# Pump_Control_Circuit.net
KiCad netlist of a schematic drawn in EAGLE
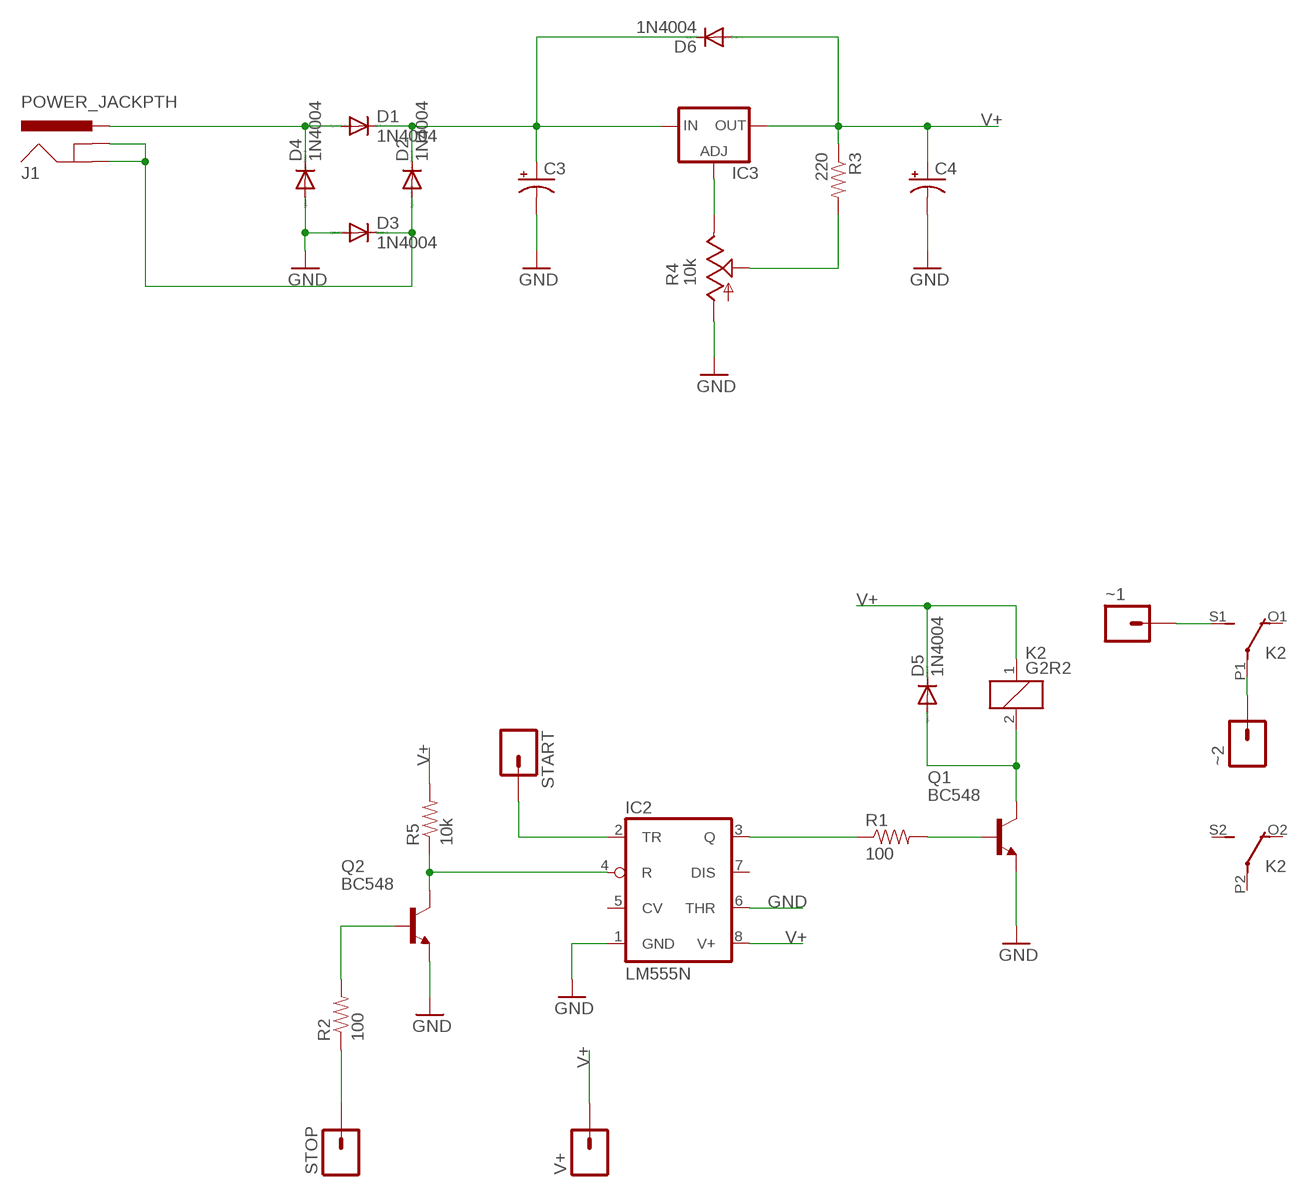
[diagram p0: schematic, sheet 1]

(export (version "E")
  (design (tool "Eeschema 10.0.6"))
  (components
    (comp (ref "C3")
      (value "CAP_POLPTH1")
      (footprint "eagle-import:CPOL-RADIAL-100UF-25V")
      (libsource (lib "eagle-import") (part "CAP_POLPTH1"))
    )
    (comp (ref "C4")
      (value "CAP_POLPTH4")
      (footprint "eagle-import:CPOL-RADIAL-1000UF-25V")
      (libsource (lib "eagle-import") (part "CAP_POLPTH4"))
    )
    (comp (ref "D1")
      (value "1N4004")
      (footprint "eagle-import:DO41-10")
      (libsource (lib "eagle-import") (part "1N4004"))
    )
    (comp (ref "D2")
      (value "1N4004")
      (footprint "eagle-import:DO41-10")
      (libsource (lib "eagle-import") (part "1N4004"))
    )
    (comp (ref "D3")
      (value "1N4004")
      (footprint "eagle-import:DO41-10")
      (libsource (lib "eagle-import") (part "1N4004"))
    )
    (comp (ref "D4")
      (value "1N4004")
      (footprint "eagle-import:DO41-10")
      (libsource (lib "eagle-import") (part "1N4004"))
    )
    (comp (ref "D5")
      (value "1N4004")
      (footprint "eagle-import:DO41-10")
      (libsource (lib "eagle-import") (part "1N4004"))
    )
    (comp (ref "D6")
      (value "1N4004")
      (footprint "eagle-import:DO41-10")
      (libsource (lib "eagle-import") (part "1N4004"))
    )
    (comp (ref "IC2")
      (value "LM555N")
      (footprint "eagle-import:DIL08")
      (libsource (lib "eagle-import") (part "555NLM"))
    )
    (comp (ref "IC3")
      (value "LM317TS")
      (footprint "eagle-import:317TS")
      (libsource (lib "eagle-import") (part "LM317TS"))
    )
    (comp (ref "J1")
      (value "POWER_JACKPTH")
      (footprint "eagle-import:POWER_JACK_PTH")
      (libsource (lib "eagle-import") (part "POWER_JACKPTH"))
    )
    (comp (ref "K2")
      (value "G2R2")
      (footprint "eagle-import:G2R2")
      (fields (field (name "MF") "OMRON COMPONENTS USA") (field (name "MPN") "G2R-2-DC6"))
      (libsource (lib "eagle-import") (part "G2R2"))
    )
    (comp (ref "Q1")
      (value "BC548")
      (footprint "eagle-import:TO92-EBC")
      (libsource (lib "eagle-import") (part "BC548"))
    )
    (comp (ref "Q2")
      (value "BC548")
      (footprint "eagle-import:TO92-EBC")
      (libsource (lib "eagle-import") (part "BC548"))
    )
    (comp (ref "R1")
      (value "100")
      (footprint "eagle-import:AXIAL-0.3")
      (libsource (lib "eagle-import") (part "SparkFun-Resistors_RESISTORAXIAL-0.3"))
    )
    (comp (ref "R2")
      (value "100")
      (footprint "eagle-import:AXIAL-0.3")
      (libsource (lib "eagle-import") (part "SparkFun-Resistors_RESISTORAXIAL-0.3"))
    )
    (comp (ref "R3")
      (value "220")
      (footprint "eagle-import:AXIAL-0.3")
      (libsource (lib "eagle-import") (part "RESISTORAXIAL-0.3"))
    )
    (comp (ref "R4")
      (value "10k")
      (footprint "eagle-import:B64Y")
      (libsource (lib "eagle-import") (part "TRIM_US-B64Y"))
    )
    (comp (ref "R5")
      (value "10k")
      (footprint "eagle-import:AXIAL-0.3")
      (libsource (lib "eagle-import") (part "SparkFun-Resistors_RESISTORAXIAL-0.3"))
    )
    (comp (ref "START")
      (value "M01PTH")
      (footprint "eagle-import:1X01")
      (libsource (lib "eagle-import") (part "M01PTH"))
    )
    (comp (ref "STOP")
      (value "M01PTH")
      (footprint "eagle-import:1X01")
      (libsource (lib "eagle-import") (part "M01PTH"))
    )
    (comp (ref "V+")
      (value "M01PTH")
      (footprint "eagle-import:1X01")
      (libsource (lib "eagle-import") (part "M01PTH"))
    )
    (comp (ref "~1")
      (value "M01PTH")
      (footprint "eagle-import:1X01")
      (libsource (lib "eagle-import") (part "M01PTH"))
    )
    (comp (ref "~2")
      (value "M01PTH")
      (footprint "eagle-import:1X01")
      (libsource (lib "eagle-import") (part "M01PTH"))
    )
  )
  (nets
    (net (code "1") (name "/V+") (class "Default")
      (node (ref "C4") (pin "+") (pinfunction "+_+") (pintype "passive"))
      (node (ref "D5") (pin "C") (pinfunction "C_C") (pintype "passive"))
      (node (ref "D6") (pin "A") (pinfunction "A_A") (pintype "passive"))
      (node (ref "IC2") (pin "8") (pinfunction "V+_8") (pintype "power_in"))
      (node (ref "IC3") (pin "2") (pinfunction "OUT_2") (pintype "passive"))
      (node (ref "K2") (pin "1") (pinfunction "1_1") (pintype "passive"))
      (node (ref "R3") (pin "P$1") (pinfunction "1_P$1") (pintype "passive"))
      (node (ref "R5") (pin "P$2") (pinfunction "2_P$2") (pintype "passive"))
      (node (ref "V+") (pin "1") (pinfunction "1_1") (pintype "passive"))
    )
    (net (code "2") (name "GND") (class "Default")
      (node (ref "C3") (pin "2") (pinfunction "-_2") (pintype "passive"))
      (node (ref "C4") (pin "-") (pinfunction "-_-") (pintype "passive"))
      (node (ref "D3") (pin "A") (pinfunction "A_A") (pintype "passive"))
      (node (ref "D4") (pin "A") (pinfunction "A_A") (pintype "passive"))
      (node (ref "IC2") (pin "1") (pinfunction "GND_1") (pintype "power_in"))
      (node (ref "IC2") (pin "6") (pinfunction "THR_6") (pintype "input"))
      (node (ref "Q1") (pin "E") (pinfunction "E_E") (pintype "passive"))
      (node (ref "Q2") (pin "E") (pinfunction "E_E") (pintype "passive"))
      (node (ref "R4") (pin "A") (pinfunction "A_A") (pintype "passive"))
    )
    (net (code "3") (name "Net-(C3-+)") (class "Default")
      (node (ref "C3") (pin "1") (pinfunction "+_1") (pintype "passive"))
      (node (ref "D1") (pin "C") (pinfunction "C_C") (pintype "passive"))
      (node (ref "D2") (pin "C") (pinfunction "C_C") (pintype "passive"))
      (node (ref "D6") (pin "C") (pinfunction "C_C") (pintype "passive"))
      (node (ref "IC3") (pin "3") (pinfunction "IN_3") (pintype "input"))
    )
    (net (code "4") (name "Net-(D1-PadA)") (class "Default")
      (node (ref "D1") (pin "A") (pinfunction "A_A") (pintype "passive"))
      (node (ref "D4") (pin "C") (pinfunction "C_C") (pintype "passive"))
      (node (ref "J1") (pin "PWR") (pinfunction "PWR_PWR") (pintype "bidirectional"))
    )
    (net (code "5") (name "Net-(D2-PadA)") (class "Default")
      (node (ref "D2") (pin "A") (pinfunction "A_A") (pintype "passive"))
      (node (ref "D3") (pin "C") (pinfunction "C_C") (pintype "passive"))
      (node (ref "J1") (pin "GND") (pinfunction "GND_GND") (pintype "bidirectional"))
      (node (ref "J1") (pin "GNDBREAK") (pinfunction "GNDBREAK_GNDBREAK") (pintype "bidirectional"))
    )
    (net (code "6") (name "Net-(D5-PadA)") (class "Default")
      (node (ref "D5") (pin "A") (pinfunction "A_A") (pintype "passive"))
      (node (ref "K2") (pin "2") (pinfunction "2_2") (pintype "passive"))
      (node (ref "Q1") (pin "C") (pinfunction "C_C") (pintype "passive"))
    )
    (net (code "7") (name "Net-(IC2-Q)") (class "Default")
      (node (ref "IC2") (pin "3") (pinfunction "Q_3") (pintype "output"))
      (node (ref "R1") (pin "P$1") (pinfunction "1_P$1") (pintype "passive"))
    )
    (net (code "8") (name "Net-(IC2-R)") (class "Default")
      (node (ref "IC2") (pin "4") (pinfunction "R_4") (pintype "input"))
      (node (ref "Q2") (pin "C") (pinfunction "C_C") (pintype "passive"))
      (node (ref "R5") (pin "P$1") (pinfunction "1_P$1") (pintype "passive"))
    )
    (net (code "9") (name "Net-(IC2-TR)") (class "Default")
      (node (ref "IC2") (pin "2") (pinfunction "TR_2") (pintype "input"))
      (node (ref "START") (pin "1") (pinfunction "1_1") (pintype "passive"))
    )
    (net (code "10") (name "Net-(IC3-ADJ)") (class "Default")
      (node (ref "IC3") (pin "1") (pinfunction "ADJ_1") (pintype "input"))
      (node (ref "R4") (pin "E") (pinfunction "E_E") (pintype "passive"))
    )
    (net (code "11") (name "Net-(K2B-P)") (class "Default")
      (node (ref "K2") (pin "P1") (pinfunction "P_P1") (pintype "passive"))
      (node (ref "~2") (pin "1") (pinfunction "1_1") (pintype "passive"))
    )
    (net (code "12") (name "Net-(K2B-S)") (class "Default")
      (node (ref "K2") (pin "S1") (pinfunction "S_S1") (pintype "passive"))
      (node (ref "~1") (pin "1") (pinfunction "1_1") (pintype "passive"))
    )
    (net (code "13") (name "Net-(R1-2)") (class "Default")
      (node (ref "Q1") (pin "B") (pinfunction "B_B") (pintype "passive"))
      (node (ref "R1") (pin "P$2") (pinfunction "2_P$2") (pintype "passive"))
    )
    (net (code "14") (name "Net-(R2-1)") (class "Default")
      (node (ref "R2") (pin "P$1") (pinfunction "1_P$1") (pintype "passive"))
      (node (ref "STOP") (pin "1") (pinfunction "1_1") (pintype "passive"))
    )
    (net (code "15") (name "Net-(R2-2)") (class "Default")
      (node (ref "Q2") (pin "B") (pinfunction "B_B") (pintype "passive"))
      (node (ref "R2") (pin "P$2") (pinfunction "2_P$2") (pintype "passive"))
    )
    (net (code "16") (name "Net-(R3-2)") (class "Default")
      (node (ref "R3") (pin "P$2") (pinfunction "2_P$2") (pintype "passive"))
      (node (ref "R4") (pin "S") (pinfunction "S_S") (pintype "passive"))
    )
    (net (code "17") (name "unconnected-(IC2-CV-Pad5)") (class "Default")
      (node (ref "IC2") (pin "5") (pinfunction "CV_5") (pintype "input"))
    )
    (net (code "18") (name "unconnected-(IC2-DIS-Pad7)") (class "Default")
      (node (ref "IC2") (pin "7") (pinfunction "DIS_7") (pintype "input"))
    )
    (net (code "19") (name "unconnected-(K2B-O-PadO1)") (class "Default")
      (node (ref "K2") (pin "O1") (pinfunction "O_O1") (pintype "passive"))
    )
    (net (code "20") (name "unconnected-(K2C-O-PadO2)") (class "Default")
      (node (ref "K2") (pin "O2") (pinfunction "O_O2") (pintype "passive"))
    )
    (net (code "21") (name "unconnected-(K2C-P-PadP2)") (class "Default")
      (node (ref "K2") (pin "P2") (pinfunction "P_P2") (pintype "passive"))
    )
    (net (code "22") (name "unconnected-(K2C-S-PadS2)") (class "Default")
      (node (ref "K2") (pin "S2") (pinfunction "S_S2") (pintype "passive"))
    )
  )
)
